# Elektroskate_Teensy_08_08_2014.net
KiCad netlist of a schematic drawn in EAGLE
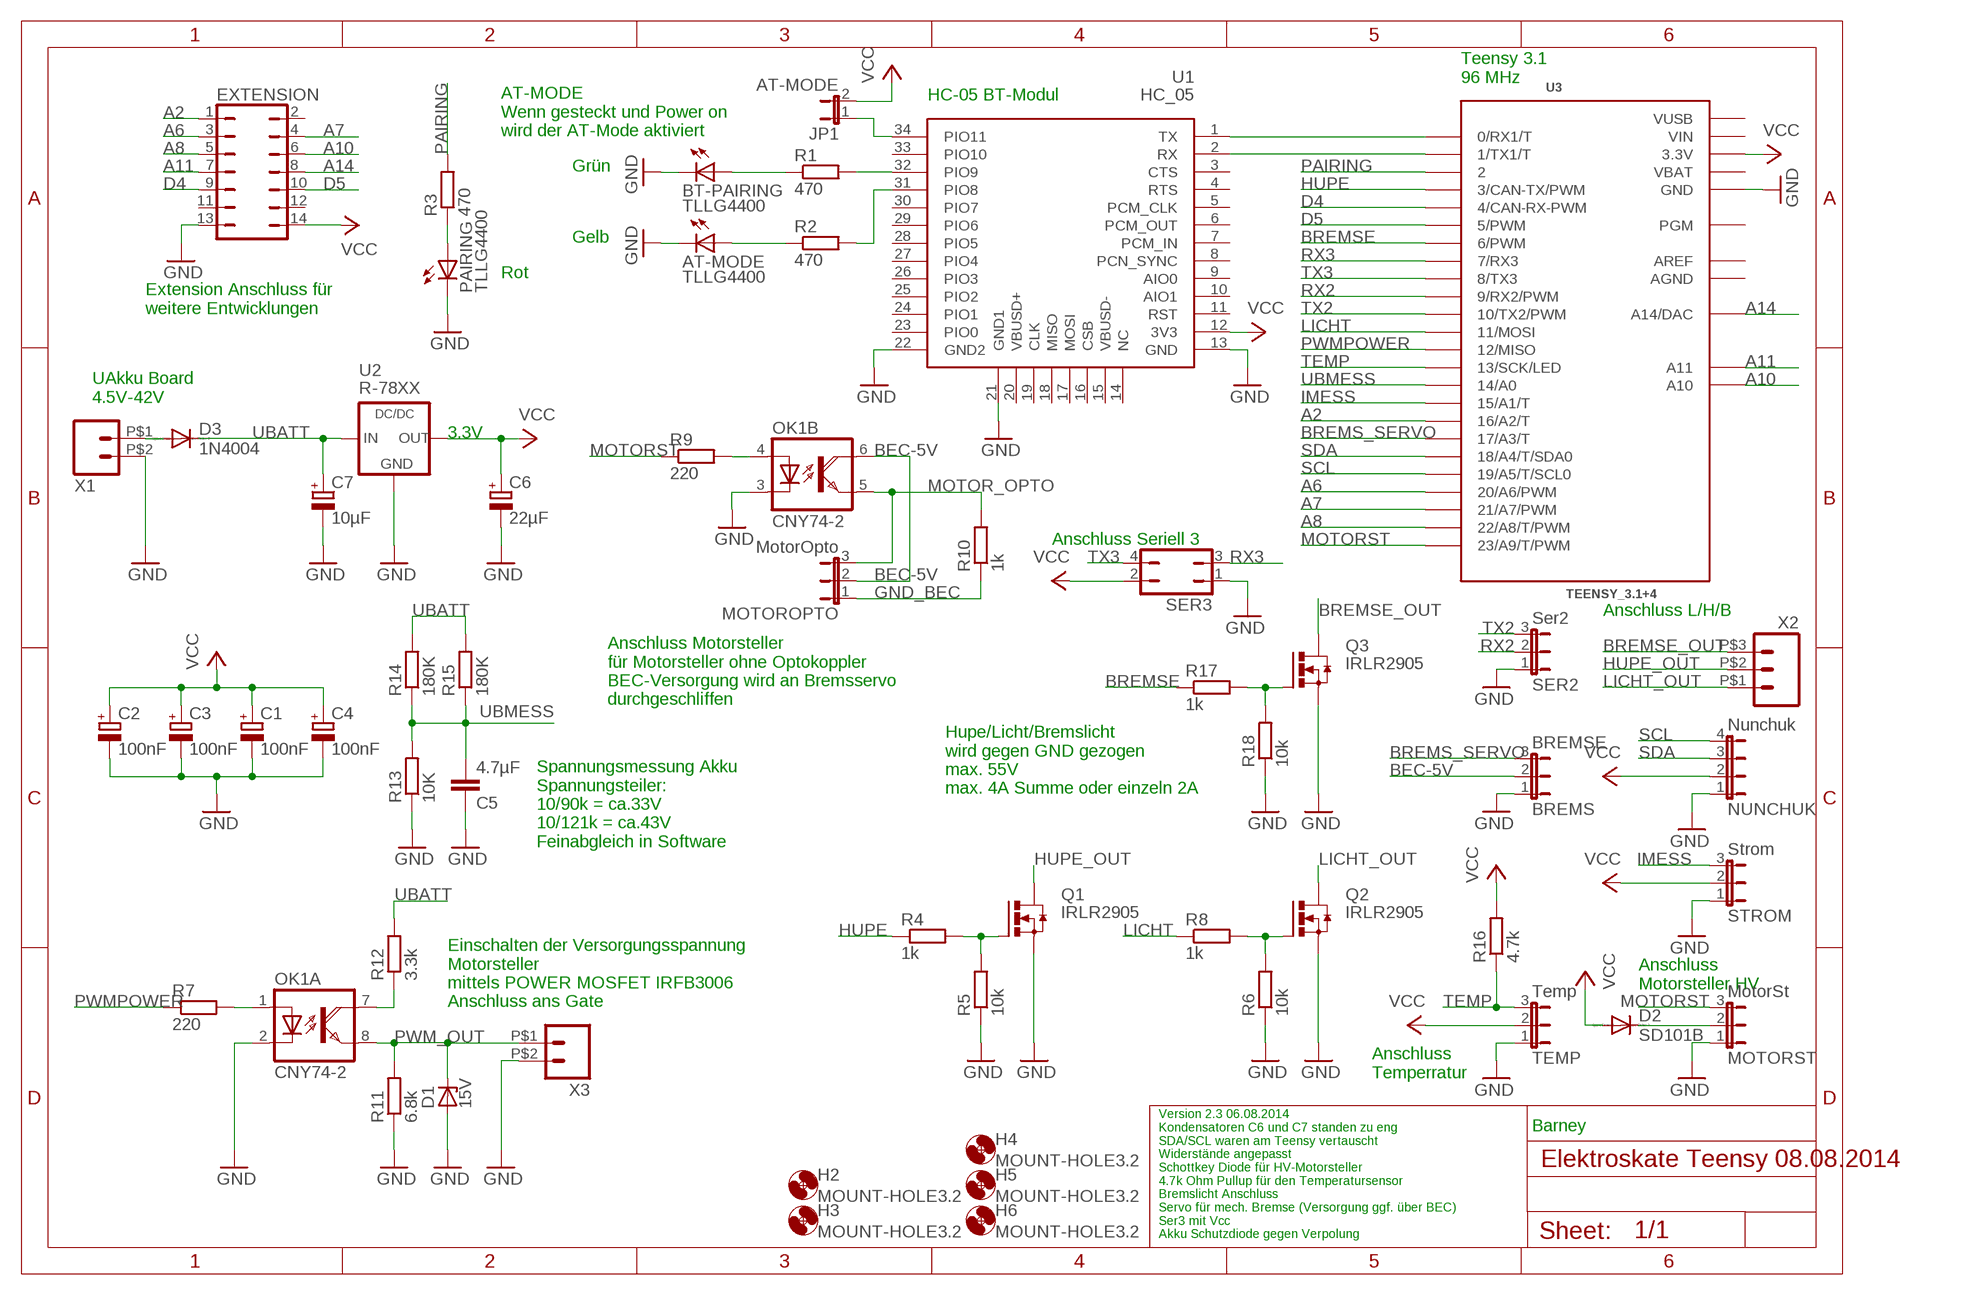
[diagram p0: schematic, sheet 1]

(export (version "E")
  (design (tool "Eeschema 10.0.6"))
  (components
    (comp (ref "AT-MODE")
      (value "TLLG4400")
      (footprint "eagle-import:LED3MM")
      (fields (field (name "MF") "VISHAY SEMICONDUCTOR"))
      (libsource (lib "eagle-import") (part "TLLG4400"))
    )
    (comp (ref "BREMS")
      (value "BREMSE")
      (footprint "eagle-import:JP2")
      (libsource (lib "eagle-import") (part "JP2E"))
    )
    (comp (ref "BT-PAIRING")
      (value "TLLG4400")
      (footprint "eagle-import:LED3MM")
      (fields (field (name "MF") "VISHAY SEMICONDUCTOR"))
      (libsource (lib "eagle-import") (part "TLLG4400"))
    )
    (comp (ref "C1")
      (value "100nF")
      (footprint "eagle-import:B45181A")
      (libsource (lib "eagle-import") (part "CPOL-EUB45181A"))
    )
    (comp (ref "C2")
      (value "100nF")
      (footprint "eagle-import:B45181A")
      (libsource (lib "eagle-import") (part "CPOL-EUB45181A"))
    )
    (comp (ref "C3")
      (value "100nF")
      (footprint "eagle-import:B45181A")
      (libsource (lib "eagle-import") (part "CPOL-EUB45181A"))
    )
    (comp (ref "C4")
      (value "100nF")
      (footprint "eagle-import:B45181A")
      (libsource (lib "eagle-import") (part "CPOL-EUB45181A"))
    )
    (comp (ref "C5")
      (value "4.7µF")
      (footprint "eagle-import:C025-024X044")
      (libsource (lib "eagle-import") (part "C-EU025-024X044"))
    )
    (comp (ref "C6")
      (value "22µF")
      (footprint "eagle-import:E2,5-5")
      (libsource (lib "eagle-import") (part "CPOL-EUE2.5-5"))
    )
    (comp (ref "C7")
      (value "10µF")
      (footprint "eagle-import:E2-4")
      (libsource (lib "eagle-import") (part "CPOL-EUE2-4"))
    )
    (comp (ref "D1")
      (value "15V")
      (footprint "eagle-import:DO35Z10")
      (libsource (lib "eagle-import") (part "ZPD"))
    )
    (comp (ref "D2")
      (value "SD101B")
      (footprint "eagle-import:SOD123")
      (libsource (lib "eagle-import") (part "MBR0520LT"))
    )
    (comp (ref "D3")
      (value "1N4004")
      (footprint "eagle-import:DO41-10")
      (libsource (lib "eagle-import") (part "1N4004"))
    )
    (comp (ref "EXTENSION")
      (value "JP7Q")
      (footprint "eagle-import:JP7Q")
      (libsource (lib "eagle-import") (part "JP7Q"))
    )
    (comp (ref "H2")
      (value "MOUNT-HOLE3.2")
      (footprint "eagle-import:3,2")
      (libsource (lib "eagle-import") (part "MOUNT-HOLE3.2"))
    )
    (comp (ref "H3")
      (value "MOUNT-HOLE3.2")
      (footprint "eagle-import:3,2")
      (libsource (lib "eagle-import") (part "MOUNT-HOLE3.2"))
    )
    (comp (ref "H4")
      (value "MOUNT-HOLE3.2")
      (footprint "eagle-import:3,2")
      (libsource (lib "eagle-import") (part "MOUNT-HOLE3.2"))
    )
    (comp (ref "H5")
      (value "MOUNT-HOLE3.2")
      (footprint "eagle-import:3,2")
      (libsource (lib "eagle-import") (part "MOUNT-HOLE3.2"))
    )
    (comp (ref "H6")
      (value "MOUNT-HOLE3.2")
      (footprint "eagle-import:3,2")
      (libsource (lib "eagle-import") (part "MOUNT-HOLE3.2"))
    )
    (comp (ref "JP1")
      (value "AT-MODE")
      (footprint "eagle-import:JP1")
      (libsource (lib "eagle-import") (part "JP1E"))
    )
    (comp (ref "MOTOROPTO")
      (value "MotorOpto")
      (footprint "eagle-import:JP2")
      (libsource (lib "eagle-import") (part "JP2E"))
    )
    (comp (ref "MOTORST")
      (value "MotorSt")
      (footprint "eagle-import:JP2")
      (libsource (lib "eagle-import") (part "JP2E"))
    )
    (comp (ref "NUNCHUK")
      (value "Nunchuk")
      (footprint "eagle-import:JP4")
      (libsource (lib "eagle-import") (part "JP4E"))
    )
    (comp (ref "OK1")
      (value "CNY74-2")
      (footprint "eagle-import:DIL08")
      (fields (field (name "MF") "VISHAY/TELEFUNKEN") (field (name "MPN") "ILD30"))
      (libsource (lib "eagle-import") (part "ILD30"))
    )
    (comp (ref "PAIRING")
      (value "TLLG4400")
      (footprint "eagle-import:LED3MM")
      (fields (field (name "MF") "VISHAY SEMICONDUCTOR"))
      (libsource (lib "eagle-import") (part "TLLG4400"))
    )
    (comp (ref "Q1")
      (value "IRLR2905")
      (footprint "eagle-import:D-PAK_TO252AA")
      (libsource (lib "eagle-import") (part "IRLR2905"))
    )
    (comp (ref "Q2")
      (value "IRLR2905")
      (footprint "eagle-import:D-PAK_TO252AA")
      (libsource (lib "eagle-import") (part "IRLR2905"))
    )
    (comp (ref "Q3")
      (value "IRLR2905")
      (footprint "eagle-import:D-PAK_TO252AA")
      (libsource (lib "eagle-import") (part "IRLR2905"))
    )
    (comp (ref "R1")
      (value "470")
      (footprint "eagle-import:0207_10")
      (libsource (lib "eagle-import") (part "R-EU_0207/10"))
    )
    (comp (ref "R2")
      (value "470")
      (footprint "eagle-import:0207_10")
      (libsource (lib "eagle-import") (part "R-EU_0207/10"))
    )
    (comp (ref "R3")
      (value "470")
      (footprint "eagle-import:0207_10")
      (libsource (lib "eagle-import") (part "R-EU_0207/10"))
    )
    (comp (ref "R4")
      (value "1k")
      (footprint "eagle-import:0207_10")
      (libsource (lib "eagle-import") (part "R-EU_0207/10"))
    )
    (comp (ref "R5")
      (value "10k")
      (footprint "eagle-import:0207_10")
      (libsource (lib "eagle-import") (part "R-EU_0207/10"))
    )
    (comp (ref "R6")
      (value "10k")
      (footprint "eagle-import:0207_10")
      (libsource (lib "eagle-import") (part "R-EU_0207/10"))
    )
    (comp (ref "R7")
      (value "220")
      (footprint "eagle-import:0207_10")
      (libsource (lib "eagle-import") (part "R-EU_0207/10"))
    )
    (comp (ref "R8")
      (value "1k")
      (footprint "eagle-import:0207_10")
      (libsource (lib "eagle-import") (part "R-EU_0207/10"))
    )
    (comp (ref "R9")
      (value "220")
      (footprint "eagle-import:0207_10")
      (libsource (lib "eagle-import") (part "R-EU_0207/10"))
    )
    (comp (ref "R10")
      (value "1k")
      (footprint "eagle-import:0207_10")
      (libsource (lib "eagle-import") (part "R-EU_0207/10"))
    )
    (comp (ref "R11")
      (value "6.8k")
      (footprint "eagle-import:0207_10")
      (libsource (lib "eagle-import") (part "R-EU_0207/10"))
    )
    (comp (ref "R12")
      (value "3.3k")
      (footprint "eagle-import:0207_10")
      (libsource (lib "eagle-import") (part "R-EU_0207/10"))
    )
    (comp (ref "R13")
      (value "10K")
      (footprint "eagle-import:0207_10")
      (libsource (lib "eagle-import") (part "R-EU_0207/10"))
    )
    (comp (ref "R14")
      (value "180K")
      (footprint "eagle-import:0207_10")
      (libsource (lib "eagle-import") (part "R-EU_0207/10"))
    )
    (comp (ref "R15")
      (value "180K")
      (footprint "eagle-import:0207_10")
      (libsource (lib "eagle-import") (part "R-EU_0207/10"))
    )
    (comp (ref "R16")
      (value "4.7k")
      (footprint "eagle-import:R0805")
      (libsource (lib "eagle-import") (part "R-EU_R0805"))
    )
    (comp (ref "R17")
      (value "1k")
      (footprint "eagle-import:0207_10")
      (libsource (lib "eagle-import") (part "R-EU_0207/10"))
    )
    (comp (ref "R18")
      (value "10k")
      (footprint "eagle-import:0207_10")
      (libsource (lib "eagle-import") (part "R-EU_0207/10"))
    )
    (comp (ref "SER2")
      (value "Ser2")
      (footprint "eagle-import:JP2")
      (libsource (lib "eagle-import") (part "JP2E"))
    )
    (comp (ref "SER3")
      (value "JP2Q")
      (footprint "eagle-import:JP2Q")
      (libsource (lib "eagle-import") (part "JP2Q"))
    )
    (comp (ref "STROM")
      (value "Strom")
      (footprint "eagle-import:JP2")
      (libsource (lib "eagle-import") (part "JP2E"))
    )
    (comp (ref "TEMP")
      (value "Temp")
      (footprint "eagle-import:JP2")
      (libsource (lib "eagle-import") (part "JP2E"))
    )
    (comp (ref "U1")
      (value "HC_05")
      (footprint "eagle-import:BLUETOOTH_SMD")
      (libsource (lib "eagle-import") (part "HC_05"))
    )
    (comp (ref "U2")
      (value "R-78XX")
      (footprint "eagle-import:R-78XX")
      (fields (field (name "SPANNUNG") "3.3V"))
      (libsource (lib "eagle-import") (part "R-78XX"))
    )
    (comp (ref "U3")
      (value "TEENSY_3.1+4")
      (footprint "eagle-import:TEENSY_3.1+4")
      (libsource (lib "eagle-import") (part "TEENSY_3.1+4"))
    )
    (comp (ref "X1")
      (value "PSS254_2GEWINKELT")
      (footprint "eagle-import:02W")
      (libsource (lib "eagle-import") (part "PSS254_2GEWINKELT"))
    )
    (comp (ref "X2")
      (value "PSS254_3GEWINKELT")
      (footprint "eagle-import:03W")
      (libsource (lib "eagle-import") (part "PSS254_3GEWINKELT"))
    )
    (comp (ref "X3")
      (value "PSS254_2GEWINKELT")
      (footprint "eagle-import:02W")
      (libsource (lib "eagle-import") (part "PSS254_2GEWINKELT"))
    )
  )
  (nets
    (net (code "1") (name "/A2") (class "Default")
      (node (ref "EXTENSION") (pin "1") (pinfunction "1_1") (pintype "passive"))
      (node (ref "U3") (pin "16/A2") (pinfunction "16/A2/T_16/A2") (pintype "bidirectional"))
    )
    (net (code "2") (name "/A6") (class "Default")
      (node (ref "EXTENSION") (pin "3") (pinfunction "3_3") (pintype "passive"))
      (node (ref "U3") (pin "20/A6") (pinfunction "20/A6/PWM_20/A6") (pintype "bidirectional"))
    )
    (net (code "3") (name "/A7") (class "Default")
      (node (ref "EXTENSION") (pin "4") (pinfunction "4_4") (pintype "passive"))
      (node (ref "U3") (pin "21/A7") (pinfunction "21/A7/PWM_21/A7") (pintype "bidirectional"))
    )
    (net (code "4") (name "/A8") (class "Default")
      (node (ref "EXTENSION") (pin "5") (pinfunction "5_5") (pintype "passive"))
      (node (ref "U3") (pin "22/A8") (pinfunction "22/A8/T/PWM_22/A8") (pintype "bidirectional"))
    )
    (net (code "5") (name "/A10") (class "Default")
      (node (ref "EXTENSION") (pin "6") (pinfunction "6_6") (pintype "passive"))
      (node (ref "U3") (pin "A10") (pinfunction "A10_A10") (pintype "bidirectional"))
    )
    (net (code "6") (name "/A11") (class "Default")
      (node (ref "EXTENSION") (pin "7") (pinfunction "7_7") (pintype "passive"))
      (node (ref "U3") (pin "A11") (pinfunction "A11_A11") (pintype "bidirectional"))
    )
    (net (code "7") (name "/A14") (class "Default")
      (node (ref "EXTENSION") (pin "8") (pinfunction "8_8") (pintype "passive"))
      (node (ref "U3") (pin "A14") (pinfunction "A14/DAC_A14") (pintype "bidirectional"))
    )
    (net (code "8") (name "/AGND") (class "Default")
      (node (ref "U3") (pin "AGND") (pinfunction "AGND_AGND") (pintype "power_in"))
    )
    (net (code "9") (name "/AREF") (class "Default")
      (node (ref "U3") (pin "AREF") (pinfunction "AREF_AREF") (pintype "power_in"))
    )
    (net (code "10") (name "/BEC-5V") (class "Default")
      (node (ref "BREMS") (pin "2") (pinfunction "2_2") (pintype "passive"))
      (node (ref "MOTOROPTO") (pin "2") (pinfunction "2_2") (pintype "passive"))
      (node (ref "OK1") (pin "6") (pinfunction "COL_6") (pintype "passive"))
    )
    (net (code "11") (name "/BREMSE") (class "Default")
      (node (ref "R17") (pin "1") (pinfunction "1_1") (pintype "passive"))
      (node (ref "U3") (pin "6") (pinfunction "6/PWM_6") (pintype "bidirectional"))
    )
    (net (code "12") (name "/BREMSE_OUT") (class "Default")
      (node (ref "Q3") (pin "4") (pinfunction "D_4") (pintype "passive"))
      (node (ref "X2") (pin "P$3") (pinfunction "3_P$3") (pintype "passive"))
    )
    (net (code "13") (name "/BREMS_SERVO") (class "Default")
      (node (ref "BREMS") (pin "3") (pinfunction "3_3") (pintype "passive"))
      (node (ref "U3") (pin "17/A3") (pinfunction "17/A3/T_17/A3") (pintype "bidirectional"))
    )
    (net (code "14") (name "/D4") (class "Default")
      (node (ref "EXTENSION") (pin "9") (pinfunction "9_9") (pintype "passive"))
      (node (ref "U3") (pin "4") (pinfunction "4/CAN-RX-PWM_4") (pintype "bidirectional"))
    )
    (net (code "15") (name "/D5") (class "Default")
      (node (ref "EXTENSION") (pin "10") (pinfunction "10_10") (pintype "passive"))
      (node (ref "U3") (pin "5") (pinfunction "5/PWM_5") (pintype "bidirectional"))
    )
    (net (code "16") (name "/GND_BEC") (class "Default")
      (node (ref "MOTOROPTO") (pin "1") (pinfunction "1_1") (pintype "passive"))
      (node (ref "R10") (pin "1") (pinfunction "1_1") (pintype "passive"))
    )
    (net (code "17") (name "/HUPE") (class "Default")
      (node (ref "R4") (pin "1") (pinfunction "1_1") (pintype "passive"))
      (node (ref "U3") (pin "3") (pinfunction "3/CAN-TX/PWM_3") (pintype "bidirectional"))
    )
    (net (code "18") (name "/HUPE_OUT") (class "Default")
      (node (ref "Q1") (pin "4") (pinfunction "D_4") (pintype "passive"))
      (node (ref "X2") (pin "P$2") (pinfunction "2_P$2") (pintype "passive"))
    )
    (net (code "19") (name "/IMESS") (class "Default")
      (node (ref "STROM") (pin "3") (pinfunction "3_3") (pintype "passive"))
      (node (ref "U3") (pin "15/A1") (pinfunction "15/A1/T_15/A1") (pintype "bidirectional"))
    )
    (net (code "20") (name "/LICHT") (class "Default")
      (node (ref "R8") (pin "1") (pinfunction "1_1") (pintype "passive"))
      (node (ref "U3") (pin "11") (pinfunction "11/MOSI_11") (pintype "bidirectional"))
    )
    (net (code "21") (name "/LICHT_OUT") (class "Default")
      (node (ref "Q2") (pin "4") (pinfunction "D_4") (pintype "passive"))
      (node (ref "X2") (pin "P$1") (pinfunction "1_P$1") (pintype "passive"))
    )
    (net (code "22") (name "/MOTORST") (class "Default")
      (node (ref "MOTORST") (pin "3") (pinfunction "3_3") (pintype "passive"))
      (node (ref "R9") (pin "1") (pinfunction "1_1") (pintype "passive"))
      (node (ref "U3") (pin "23/A9") (pinfunction "23/A9/T/PWM_23/A9") (pintype "bidirectional"))
    )
    (net (code "23") (name "/MOTOR_OPTO") (class "Default")
      (node (ref "MOTOROPTO") (pin "3") (pinfunction "3_3") (pintype "passive"))
      (node (ref "OK1") (pin "5") (pinfunction "EMI_5") (pintype "passive"))
      (node (ref "R10") (pin "2") (pinfunction "2_2") (pintype "passive"))
    )
    (net (code "24") (name "/PAIRING") (class "Default")
      (node (ref "R3") (pin "2") (pinfunction "2_2") (pintype "passive"))
      (node (ref "U3") (pin "2") (pinfunction "2_2") (pintype "bidirectional"))
    )
    (net (code "25") (name "/PWMPOWER") (class "Default")
      (node (ref "R7") (pin "1") (pinfunction "1_1") (pintype "passive"))
      (node (ref "U3") (pin "12") (pinfunction "12/MISO_12") (pintype "bidirectional"))
    )
    (net (code "26") (name "/PWM_OUT") (class "Default")
      (node (ref "D1") (pin "C") (pinfunction "C_C") (pintype "passive"))
      (node (ref "OK1") (pin "8") (pinfunction "EMI_8") (pintype "passive"))
      (node (ref "R11") (pin "2") (pinfunction "2_2") (pintype "passive"))
      (node (ref "X3") (pin "P$1") (pinfunction "1_P$1") (pintype "passive"))
    )
    (net (code "27") (name "/RX2") (class "Default")
      (node (ref "SER2") (pin "2") (pinfunction "2_2") (pintype "passive"))
      (node (ref "U3") (pin "9") (pinfunction "9/RX2/PWM_9") (pintype "bidirectional"))
    )
    (net (code "28") (name "/RX3") (class "Default")
      (node (ref "SER3") (pin "3") (pinfunction "3_3") (pintype "passive"))
      (node (ref "U3") (pin "7") (pinfunction "7/RX3_7") (pintype "bidirectional"))
    )
    (net (code "29") (name "/SCL") (class "Default")
      (node (ref "NUNCHUK") (pin "4") (pinfunction "4_4") (pintype "passive"))
      (node (ref "U3") (pin "19/A5") (pinfunction "19/A5/T/SCL0_19/A5") (pintype "bidirectional"))
    )
    (net (code "30") (name "/SDA") (class "Default")
      (node (ref "NUNCHUK") (pin "3") (pinfunction "3_3") (pintype "passive"))
      (node (ref "U3") (pin "18/A4") (pinfunction "18/A4/T/SDA0_18/A4") (pintype "bidirectional"))
    )
    (net (code "31") (name "/TEMP") (class "Default")
      (node (ref "R16") (pin "1") (pinfunction "1_1") (pintype "passive"))
      (node (ref "TEMP") (pin "3") (pinfunction "3_3") (pintype "passive"))
      (node (ref "U3") (pin "13") (pinfunction "13/SCK/LED_13") (pintype "bidirectional"))
    )
    (net (code "32") (name "/TX2") (class "Default")
      (node (ref "SER2") (pin "3") (pinfunction "3_3") (pintype "passive"))
      (node (ref "U3") (pin "10") (pinfunction "10/TX2/PWM_10") (pintype "bidirectional"))
    )
    (net (code "33") (name "/TX3") (class "Default")
      (node (ref "SER3") (pin "4") (pinfunction "4_4") (pintype "passive"))
      (node (ref "U3") (pin "8") (pinfunction "8/TX3_8") (pintype "bidirectional"))
    )
    (net (code "34") (name "/UBATT") (class "Default")
      (node (ref "C7") (pin "+") (pinfunction "+_+") (pintype "passive"))
      (node (ref "D3") (pin "C") (pinfunction "C_C") (pintype "passive"))
      (node (ref "R12") (pin "2") (pinfunction "2_2") (pintype "passive"))
      (node (ref "R14") (pin "2") (pinfunction "2_2") (pintype "passive"))
      (node (ref "R15") (pin "2") (pinfunction "2_2") (pintype "passive"))
      (node (ref "U2") (pin "1") (pinfunction "IN_1") (pintype "input"))
    )
    (net (code "35") (name "/UBMESS") (class "Default")
      (node (ref "C5") (pin "2") (pinfunction "2_2") (pintype "passive"))
      (node (ref "R13") (pin "2") (pinfunction "2_2") (pintype "passive"))
      (node (ref "R14") (pin "1") (pinfunction "1_1") (pintype "passive"))
      (node (ref "R15") (pin "1") (pinfunction "1_1") (pintype "passive"))
      (node (ref "U3") (pin "14/A0") (pinfunction "14/A0_14/A0") (pintype "bidirectional"))
    )
    (net (code "36") (name "/VBAT") (class "Default")
      (node (ref "U3") (pin "VBAT") (pinfunction "VBAT_VBAT") (pintype "power_in"))
    )
    (net (code "37") (name "/VIN") (class "Default")
      (node (ref "U3") (pin "VIN") (pinfunction "VIN_VIN") (pintype "power_in"))
    )
    (net (code "38") (name "/VUSB") (class "Default")
      (node (ref "U3") (pin "VUSB") (pinfunction "VUSB_VUSB") (pintype "power_in"))
    )
    (net (code "39") (name "GND") (class "Default")
      (node (ref "AT-MODE") (pin "K") (pinfunction "C_K") (pintype "passive"))
      (node (ref "BREMS") (pin "1") (pinfunction "1_1") (pintype "passive"))
      (node (ref "BT-PAIRING") (pin "K") (pinfunction "C_K") (pintype "passive"))
      (node (ref "C1") (pin "-") (pinfunction "-_-") (pintype "passive"))
      (node (ref "C2") (pin "-") (pinfunction "-_-") (pintype "passive"))
      (node (ref "C3") (pin "-") (pinfunction "-_-") (pintype "passive"))
      (node (ref "C4") (pin "-") (pinfunction "-_-") (pintype "passive"))
      (node (ref "C5") (pin "1") (pinfunction "1_1") (pintype "passive"))
      (node (ref "C6") (pin "-") (pinfunction "-_-") (pintype "passive"))
      (node (ref "C7") (pin "-") (pinfunction "-_-") (pintype "passive"))
      (node (ref "D1") (pin "A") (pinfunction "A_A") (pintype "passive"))
      (node (ref "EXTENSION") (pin "13") (pinfunction "13_13") (pintype "passive"))
      (node (ref "MOTORST") (pin "1") (pinfunction "1_1") (pintype "passive"))
      (node (ref "NUNCHUK") (pin "1") (pinfunction "1_1") (pintype "passive"))
      (node (ref "OK1") (pin "2") (pinfunction "C_2") (pintype "passive"))
      (node (ref "OK1") (pin "3") (pinfunction "C_3") (pintype "passive"))
      (node (ref "PAIRING") (pin "K") (pinfunction "C_K") (pintype "passive"))
      (node (ref "Q1") (pin "3") (pinfunction "S_3") (pintype "passive"))
      (node (ref "Q2") (pin "3") (pinfunction "S_3") (pintype "passive"))
      (node (ref "Q3") (pin "3") (pinfunction "S_3") (pintype "passive"))
      (node (ref "R11") (pin "1") (pinfunction "1_1") (pintype "passive"))
      (node (ref "R13") (pin "1") (pinfunction "1_1") (pintype "passive"))
      (node (ref "R18") (pin "1") (pinfunction "1_1") (pintype "passive"))
      (node (ref "R5") (pin "1") (pinfunction "1_1") (pintype "passive"))
      (node (ref "R6") (pin "1") (pinfunction "1_1") (pintype "passive"))
      (node (ref "SER2") (pin "1") (pinfunction "1_1") (pintype "passive"))
      (node (ref "SER3") (pin "1") (pinfunction "1_1") (pintype "passive"))
      (node (ref "STROM") (pin "1") (pinfunction "1_1") (pintype "passive"))
      (node (ref "TEMP") (pin "1") (pinfunction "1_1") (pintype "passive"))
      (node (ref "U1") (pin "13") (pinfunction "GND_13") (pintype "bidirectional"))
      (node (ref "U1") (pin "21") (pinfunction "GND1_21") (pintype "bidirectional"))
      (node (ref "U1") (pin "22") (pinfunction "GND2_22") (pintype "bidirectional"))
      (node (ref "U2") (pin "2") (pinfunction "GND_2") (pintype "input"))
      (node (ref "U3") (pin "GND") (pinfunction "GND_GND") (pintype "power_in"))
      (node (ref "U3") (pin "GND1") (pinfunction "GND_GND1") (pintype "power_in"))
      (node (ref "X1") (pin "P$2") (pinfunction "2_P$2") (pintype "passive"))
      (node (ref "X3") (pin "P$2") (pinfunction "2_P$2") (pintype "passive"))
    )
    (net (code "40") (name "Net-(AT-MODE-PadA)") (class "Default")
      (node (ref "AT-MODE") (pin "A") (pinfunction "A_A") (pintype "passive"))
      (node (ref "R2") (pin "1") (pinfunction "1_1") (pintype "passive"))
    )
    (net (code "41") (name "Net-(BT-PAIRING-PadA)") (class "Default")
      (node (ref "BT-PAIRING") (pin "A") (pinfunction "A_A") (pintype "passive"))
      (node (ref "R1") (pin "1") (pinfunction "1_1") (pintype "passive"))
    )
    (net (code "42") (name "Net-(D2-PadC)") (class "Default")
      (node (ref "D2") (pin "C") (pinfunction "C_C") (pintype "passive"))
      (node (ref "MOTORST") (pin "2") (pinfunction "2_2") (pintype "passive"))
    )
    (net (code "43") (name "Net-(OK1A-A)") (class "Default")
      (node (ref "OK1") (pin "1") (pinfunction "A_1") (pintype "passive"))
      (node (ref "R7") (pin "2") (pinfunction "2_2") (pintype "passive"))
    )
    (net (code "44") (name "Net-(OK1A-COL)") (class "Default")
      (node (ref "OK1") (pin "7") (pinfunction "COL_7") (pintype "passive"))
      (node (ref "R12") (pin "1") (pinfunction "1_1") (pintype "passive"))
    )
    (net (code "45") (name "Net-(OK1B-A)") (class "Default")
      (node (ref "OK1") (pin "4") (pinfunction "A_4") (pintype "passive"))
      (node (ref "R9") (pin "2") (pinfunction "2_2") (pintype "passive"))
    )
    (net (code "46") (name "Net-(PAIRING-PadA)") (class "Default")
      (node (ref "PAIRING") (pin "A") (pinfunction "A_A") (pintype "passive"))
      (node (ref "R3") (pin "1") (pinfunction "1_1") (pintype "passive"))
    )
    (net (code "47") (name "Net-(Q1-G)") (class "Default")
      (node (ref "Q1") (pin "1") (pinfunction "G_1") (pintype "passive"))
      (node (ref "R4") (pin "2") (pinfunction "2_2") (pintype "passive"))
      (node (ref "R5") (pin "2") (pinfunction "2_2") (pintype "passive"))
    )
    (net (code "48") (name "Net-(Q2-G)") (class "Default")
      (node (ref "Q2") (pin "1") (pinfunction "G_1") (pintype "passive"))
      (node (ref "R6") (pin "2") (pinfunction "2_2") (pintype "passive"))
      (node (ref "R8") (pin "2") (pinfunction "2_2") (pintype "passive"))
    )
    (net (code "49") (name "Net-(Q3-G)") (class "Default")
      (node (ref "Q3") (pin "1") (pinfunction "G_1") (pintype "passive"))
      (node (ref "R17") (pin "2") (pinfunction "2_2") (pintype "passive"))
      (node (ref "R18") (pin "2") (pinfunction "2_2") (pintype "passive"))
    )
    (net (code "50") (name "Net-(U1-PIO8)") (class "Default")
      (node (ref "R2") (pin "2") (pinfunction "2_2") (pintype "passive"))
      (node (ref "U1") (pin "31") (pinfunction "PIO8_31") (pintype "bidirectional"))
    )
    (net (code "51") (name "Net-(U1-PIO9)") (class "Default")
      (node (ref "R1") (pin "2") (pinfunction "2_2") (pintype "passive"))
      (node (ref "U1") (pin "32") (pinfunction "PIO9_32") (pintype "bidirectional"))
    )
    (net (code "52") (name "Net-(U1-PIO11)") (class "Default")
      (node (ref "JP1") (pin "1") (pinfunction "1_1") (pintype "passive"))
      (node (ref "U1") (pin "34") (pinfunction "PIO11_34") (pintype "bidirectional"))
    )
    (net (code "53") (name "Net-(U1-RX)") (class "Default")
      (node (ref "U1") (pin "2") (pinfunction "RX_2") (pintype "bidirectional"))
      (node (ref "U3") (pin "1") (pinfunction "1/TX1/T_1") (pintype "bidirectional"))
    )
    (net (code "54") (name "Net-(U1-TX)") (class "Default")
      (node (ref "U1") (pin "1") (pinfunction "TX_1") (pintype "bidirectional"))
      (node (ref "U3") (pin "0") (pinfunction "0/RX1/T_0") (pintype "bidirectional"))
    )
    (net (code "55") (name "Net-(X1-1)") (class "Default")
      (node (ref "D3") (pin "A") (pinfunction "A_A") (pintype "passive"))
      (node (ref "X1") (pin "P$1") (pinfunction "1_P$1") (pintype "passive"))
    )
    (net (code "56") (name "VCC") (class "Default")
      (node (ref "C1") (pin "+") (pinfunction "+_+") (pintype "passive"))
      (node (ref "C2") (pin "+") (pinfunction "+_+") (pintype "passive"))
      (node (ref "C3") (pin "+") (pinfunction "+_+") (pintype "passive"))
      (node (ref "C4") (pin "+") (pinfunction "+_+") (pintype "passive"))
      (node (ref "C6") (pin "+") (pinfunction "+_+") (pintype "passive"))
      (node (ref "D2") (pin "A") (pinfunction "A_A") (pintype "passive"))
      (node (ref "EXTENSION") (pin "14") (pinfunction "14_14") (pintype "passive"))
      (node (ref "JP1") (pin "2") (pinfunction "2_2") (pintype "passive"))
      (node (ref "NUNCHUK") (pin "2") (pinfunction "2_2") (pintype "passive"))
      (node (ref "R16") (pin "2") (pinfunction "2_2") (pintype "passive"))
      (node (ref "SER3") (pin "2") (pinfunction "2_2") (pintype "passive"))
      (node (ref "STROM") (pin "2") (pinfunction "2_2") (pintype "passive"))
      (node (ref "TEMP") (pin "2") (pinfunction "2_2") (pintype "passive"))
      (node (ref "U1") (pin "12") (pinfunction "3V3_12") (pintype "bidirectional"))
      (node (ref "U2") (pin "3") (pinfunction "OUT_3") (pintype "passive"))
      (node (ref "U3") (pin "3.3V") (pinfunction "3.3V_3.3V") (pintype "power_in"))
      (node (ref "U3") (pin "3.3V1") (pinfunction "3.3V_3.3V1") (pintype "power_in"))
    )
    (net (code "57") (name "unconnected-(EXTENSION-Pad2)") (class "Default")
      (node (ref "EXTENSION") (pin "2") (pinfunction "2_2") (pintype "passive"))
    )
    (net (code "58") (name "unconnected-(EXTENSION-Pad11)") (class "Default")
      (node (ref "EXTENSION") (pin "11") (pinfunction "11_11") (pintype "passive"))
    )
    (net (code "59") (name "unconnected-(EXTENSION-Pad12)") (class "Default")
      (node (ref "EXTENSION") (pin "12") (pinfunction "12_12") (pintype "passive"))
    )
    (net (code "60") (name "unconnected-(U1-AIO0-Pad9)") (class "Default")
      (node (ref "U1") (pin "9") (pinfunction "AIO0_9") (pintype "bidirectional"))
    )
    (net (code "61") (name "unconnected-(U1-AIO1-Pad10)") (class "Default")
      (node (ref "U1") (pin "10") (pinfunction "AIO1_10") (pintype "bidirectional"))
    )
    (net (code "62") (name "unconnected-(U1-CLK-Pad19)") (class "Default")
      (node (ref "U1") (pin "19") (pinfunction "CLK_19") (pintype "bidirectional"))
    )
    (net (code "63") (name "unconnected-(U1-CSB-Pad16)") (class "Default")
      (node (ref "U1") (pin "16") (pinfunction "CSB_16") (pintype "bidirectional"))
    )
    (net (code "64") (name "unconnected-(U1-CTS-Pad3)") (class "Default")
      (node (ref "U1") (pin "3") (pinfunction "CTS_3") (pintype "bidirectional"))
    )
    (net (code "65") (name "unconnected-(U1-MISO-Pad18)") (class "Default")
      (node (ref "U1") (pin "18") (pinfunction "MISO_18") (pintype "bidirectional"))
    )
    (net (code "66") (name "unconnected-(U1-MOSI-Pad17)") (class "Default")
      (node (ref "U1") (pin "17") (pinfunction "MOSI_17") (pintype "bidirectional"))
    )
    (net (code "67") (name "unconnected-(U1-NC-Pad14)") (class "Default")
      (node (ref "U1") (pin "14") (pinfunction "NC_14") (pintype "bidirectional"))
    )
    (net (code "68") (name "unconnected-(U1-PCM_CLK-Pad5)") (class "Default")
      (node (ref "U1") (pin "5") (pinfunction "PCM_CLK_5") (pintype "bidirectional"))
    )
    (net (code "69") (name "unconnected-(U1-PCM_IN-Pad7)") (class "Default")
      (node (ref "U1") (pin "7") (pinfunction "PCM_IN_7") (pintype "bidirectional"))
    )
    (net (code "70") (name "unconnected-(U1-PCM_OUT-Pad6)") (class "Default")
      (node (ref "U1") (pin "6") (pinfunction "PCM_OUT_6") (pintype "bidirectional"))
    )
    (net (code "71") (name "unconnected-(U1-PCN_SYNC-Pad8)") (class "Default")
      (node (ref "U1") (pin "8") (pinfunction "PCN_SYNC_8") (pintype "bidirectional"))
    )
    (net (code "72") (name "unconnected-(U1-PIO0-Pad23)") (class "Default")
      (node (ref "U1") (pin "23") (pinfunction "PIO0_23") (pintype "bidirectional"))
    )
    (net (code "73") (name "unconnected-(U1-PIO1-Pad24)") (class "Default")
      (node (ref "U1") (pin "24") (pinfunction "PIO1_24") (pintype "bidirectional"))
    )
    (net (code "74") (name "unconnected-(U1-PIO2-Pad25)") (class "Default")
      (node (ref "U1") (pin "25") (pinfunction "PIO2_25") (pintype "bidirectional"))
    )
    (net (code "75") (name "unconnected-(U1-PIO3-Pad26)") (class "Default")
      (node (ref "U1") (pin "26") (pinfunction "PIO3_26") (pintype "bidirectional"))
    )
    (net (code "76") (name "unconnected-(U1-PIO4-Pad27)") (class "Default")
      (node (ref "U1") (pin "27") (pinfunction "PIO4_27") (pintype "bidirectional"))
    )
    (net (code "77") (name "unconnected-(U1-PIO5-Pad28)") (class "Default")
      (node (ref "U1") (pin "28") (pinfunction "PIO5_28") (pintype "bidirectional"))
    )
    (net (code "78") (name "unconnected-(U1-PIO6-Pad29)") (class "Default")
      (node (ref "U1") (pin "29") (pinfunction "PIO6_29") (pintype "bidirectional"))
    )
    (net (code "79") (name "unconnected-(U1-PIO7-Pad30)") (class "Default")
      (node (ref "U1") (pin "30") (pinfunction "PIO7_30") (pintype "bidirectional"))
    )
    (net (code "80") (name "unconnected-(U1-PIO10-Pad33)") (class "Default")
      (node (ref "U1") (pin "33") (pinfunction "PIO10_33") (pintype "bidirectional"))
    )
    (net (code "81") (name "unconnected-(U1-RST-Pad11)") (class "Default")
      (node (ref "U1") (pin "11") (pinfunction "RST_11") (pintype "bidirectional"))
    )
    (net (code "82") (name "unconnected-(U1-RTS-Pad4)") (class "Default")
      (node (ref "U1") (pin "4") (pinfunction "RTS_4") (pintype "bidirectional"))
    )
    (net (code "83") (name "unconnected-(U1-VBUSD+-Pad20)") (class "Default")
      (node (ref "U1") (pin "20") (pinfunction "VBUSD+_20") (pintype "bidirectional"))
    )
    (net (code "84") (name "unconnected-(U1-VBUSD--Pad15)") (class "Default")
      (node (ref "U1") (pin "15") (pinfunction "VBUSD-_15") (pintype "bidirectional"))
    )
    (net (code "85") (name "unconnected-(U3-PadPGM)") (class "Default")
      (node (ref "U3") (pin "PGM") (pinfunction "PGM_PGM") (pintype "bidirectional"))
    )
  )
)
